# peltier.net
KiCad netlist of a schematic drawn in EAGLE
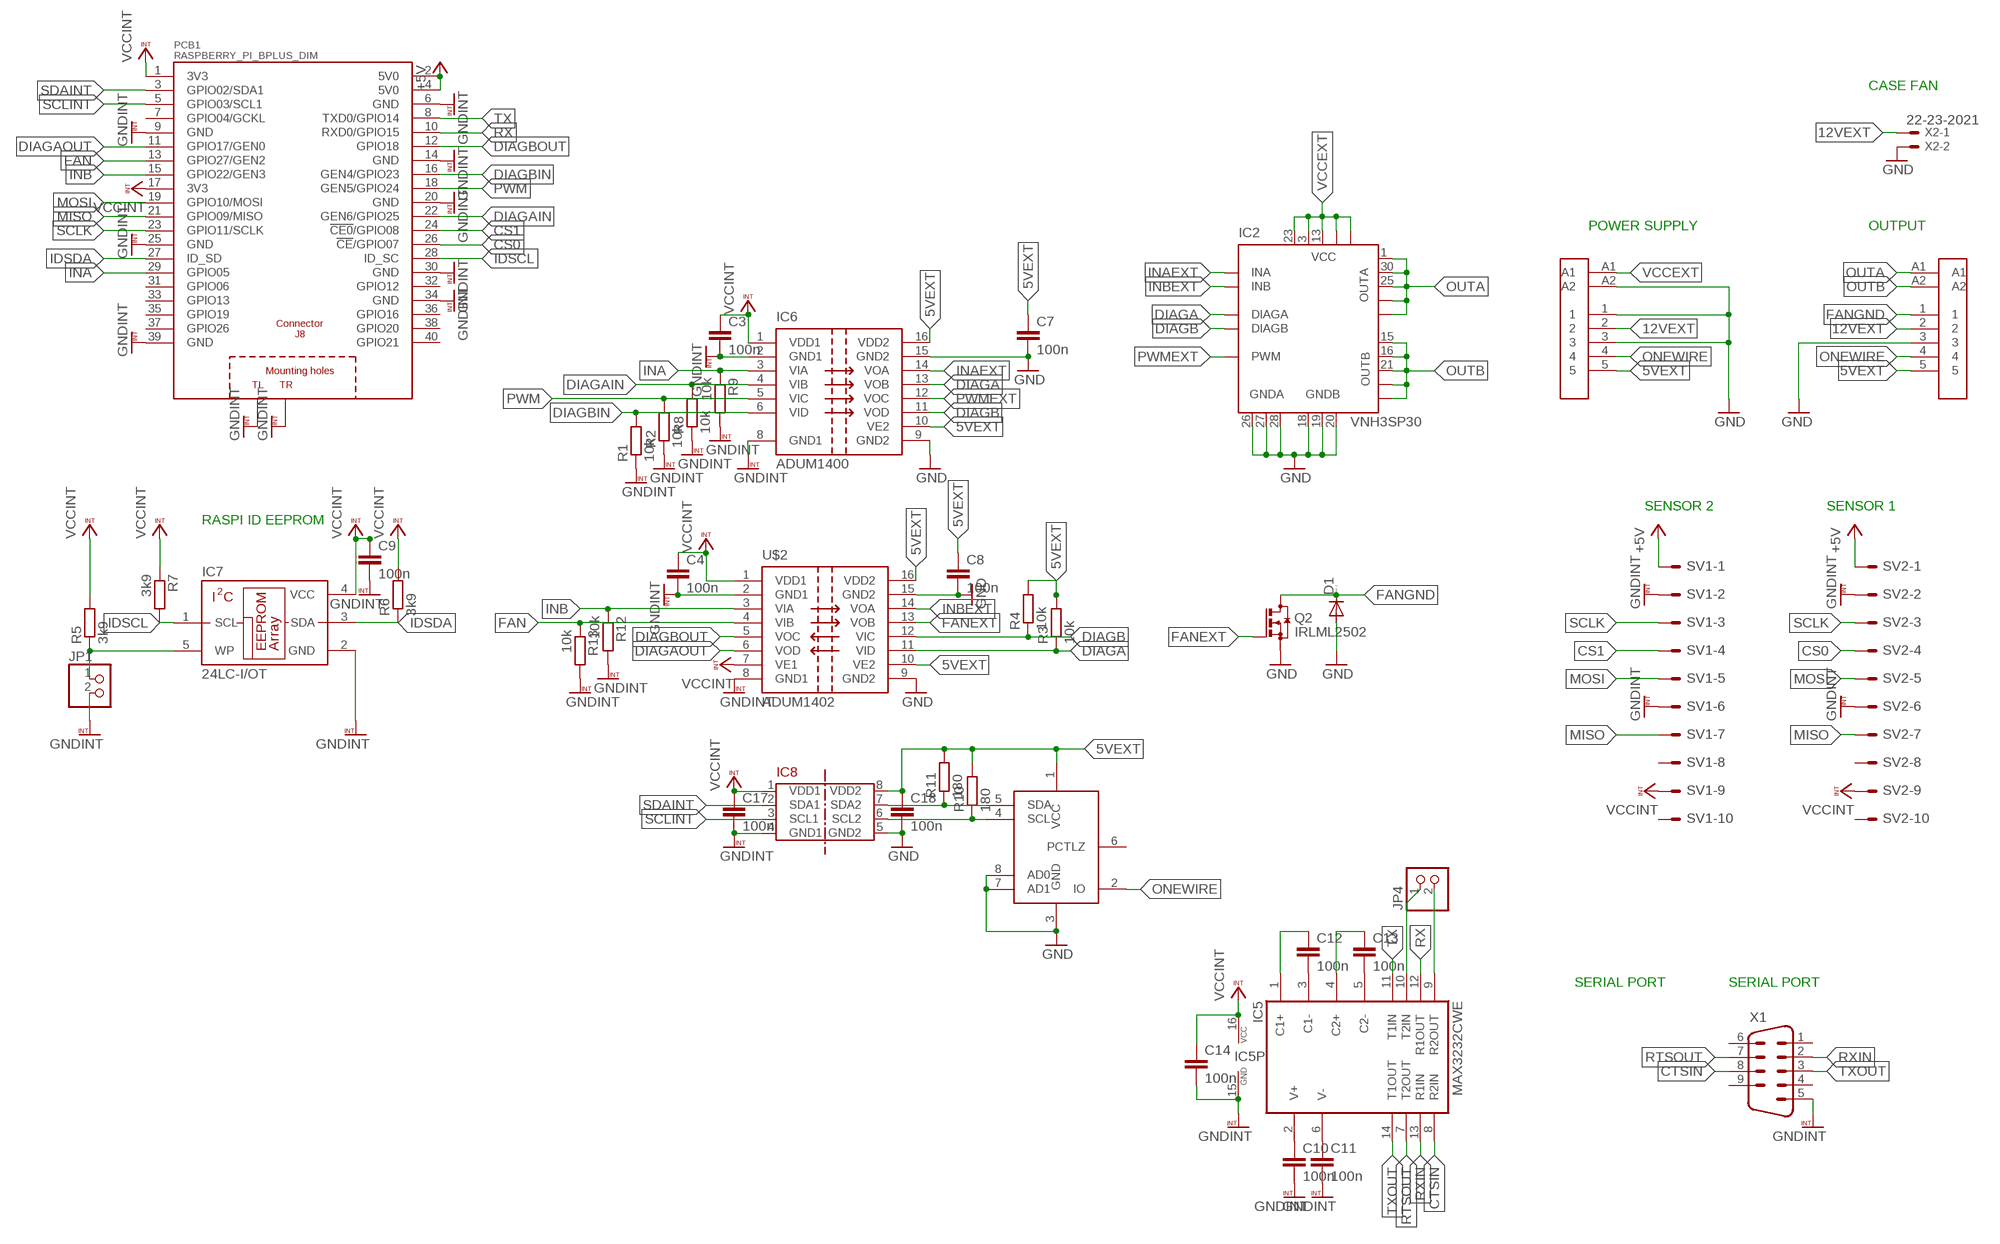
[diagram p0: schematic, sheet 1]

(export (version "E")
  (design (tool "Eeschema 10.0.6"))
  (components
    (comp (ref "C3")
      (value "100n")
      (footprint "eagle-import:C0805")
      (libsource (lib "eagle-import") (part "C-EUC0805"))
    )
    (comp (ref "C4")
      (value "100n")
      (footprint "eagle-import:C0805")
      (libsource (lib "eagle-import") (part "C-EUC0805"))
    )
    (comp (ref "C7")
      (value "100n")
      (footprint "eagle-import:C0805")
      (libsource (lib "eagle-import") (part "C-EUC0805"))
    )
    (comp (ref "C8")
      (value "100n")
      (footprint "eagle-import:C0805")
      (libsource (lib "eagle-import") (part "C-EUC0805"))
    )
    (comp (ref "C9")
      (value "100n")
      (footprint "eagle-import:C0805")
      (libsource (lib "eagle-import") (part "C-EUC0805"))
    )
    (comp (ref "C10")
      (value "100n")
      (footprint "eagle-import:C0805")
      (libsource (lib "eagle-import") (part "C-EUC0805"))
    )
    (comp (ref "C11")
      (value "100n")
      (footprint "eagle-import:C0805")
      (libsource (lib "eagle-import") (part "C-EUC0805"))
    )
    (comp (ref "C12")
      (value "100n")
      (footprint "eagle-import:C0805")
      (libsource (lib "eagle-import") (part "C-EUC0805"))
    )
    (comp (ref "C13")
      (value "100n")
      (footprint "eagle-import:C0805")
      (libsource (lib "eagle-import") (part "C-EUC0805"))
    )
    (comp (ref "C14")
      (value "100n")
      (footprint "eagle-import:C0805")
      (libsource (lib "eagle-import") (part "C-EUC0805"))
    )
    (comp (ref "C17")
      (value "100n")
      (footprint "eagle-import:C0805")
      (libsource (lib "eagle-import") (part "C-EUC0805"))
    )
    (comp (ref "C18")
      (value "100n")
      (footprint "eagle-import:C0805")
      (libsource (lib "eagle-import") (part "C-EUC0805"))
    )
    (comp (ref "D1")
      (value "DIODE-MINIMELF")
      (footprint "eagle-import:MINIMELF")
      (libsource (lib "eagle-import") (part "DIODE-MINIMELF"))
    )
    (comp (ref "IC2")
      (value "VNH3SP30")
      (footprint "eagle-import:MULTIPOWERSO-30")
      (fields (field (name "MPN") "VNH3SP30-E"))
      (libsource (lib "eagle-import") (part "VNH3SP30"))
    )
    (comp (ref "IC5")
      (value "MAX3232CWE")
      (footprint "eagle-import:SO16L")
      (fields (field (name "MF") "MAXIM") (field (name "MPN") "MAX3232CWE+"))
      (libsource (lib "eagle-import") (part "MAX3232WEC"))
    )
    (comp (ref "IC6")
      (value "ADUM1400")
      (footprint "eagle-import:SO16W")
      (libsource (lib "eagle-import") (part "ADUM1400"))
    )
    (comp (ref "IC7")
      (value "24LC-I/OT")
      (footprint "eagle-import:SOT23-5")
      (libsource (lib "eagle-import") (part "24LC-I/OT"))
    )
    (comp (ref "IC8")
      (value "ADUM1250")
      (footprint "eagle-import:SO08")
      (libsource (lib "eagle-import") (part "ADUM1250"))
    )
    (comp (ref "JP1")
      (value "PINHD-1X2")
      (footprint "eagle-import:1X02")
      (libsource (lib "eagle-import") (part "PINHD-1X2"))
    )
    (comp (ref "JP4")
      (value "PINHD-1X2")
      (footprint "eagle-import:1X02")
      (libsource (lib "eagle-import") (part "PINHD-1X2"))
    )
    (comp (ref "PCB1")
      (value "RASPBERRY_PI_BPLUS_DIM")
      (footprint "eagle-import:RASPBERRY_PI_BPLUS_DIM")
      (libsource (lib "eagle-import") (part "RASPBERRY_PI_BPLUS_DIM"))
    )
    (comp (ref "Q2")
      (value "IRLML2502")
      (footprint "eagle-import:SOT23")
      (libsource (lib "eagle-import") (part "BSS123"))
    )
    (comp (ref "R1")
      (value "10k")
      (footprint "eagle-import:R0603")
      (libsource (lib "eagle-import") (part "R-EU_R0603"))
    )
    (comp (ref "R2")
      (value "10k")
      (footprint "eagle-import:R0603")
      (libsource (lib "eagle-import") (part "R-EU_R0603"))
    )
    (comp (ref "R3")
      (value "10k")
      (footprint "eagle-import:R0805")
      (libsource (lib "eagle-import") (part "R-EU_R0805"))
    )
    (comp (ref "R4")
      (value "10k")
      (footprint "eagle-import:R0805")
      (libsource (lib "eagle-import") (part "R-EU_R0805"))
    )
    (comp (ref "R5")
      (value "3k9")
      (footprint "eagle-import:R0805")
      (libsource (lib "eagle-import") (part "R-EU_R0805"))
    )
    (comp (ref "R6")
      (value "3k9")
      (footprint "eagle-import:R0805")
      (libsource (lib "eagle-import") (part "R-EU_R0805"))
    )
    (comp (ref "R7")
      (value "3k9")
      (footprint "eagle-import:R0805")
      (libsource (lib "eagle-import") (part "R-EU_R0805"))
    )
    (comp (ref "R8")
      (value "10k")
      (footprint "eagle-import:R0603")
      (libsource (lib "eagle-import") (part "R-EU_R0603"))
    )
    (comp (ref "R9")
      (value "10k")
      (footprint "eagle-import:R0603")
      (libsource (lib "eagle-import") (part "R-EU_R0603"))
    )
    (comp (ref "R10")
      (value "180")
      (footprint "eagle-import:R0805")
      (libsource (lib "eagle-import") (part "R-EU_R0805"))
    )
    (comp (ref "R11")
      (value "180")
      (footprint "eagle-import:R0805")
      (libsource (lib "eagle-import") (part "R-EU_R0805"))
    )
    (comp (ref "R12")
      (value "10k")
      (footprint "eagle-import:R0603")
      (libsource (lib "eagle-import") (part "R-EU_R0603"))
    )
    (comp (ref "R13")
      (value "10k")
      (footprint "eagle-import:R0603")
      (libsource (lib "eagle-import") (part "R-EU_R0603"))
    )
    (comp (ref "SV1")
      (value "ML10E")
      (footprint "eagle-import:ML10")
      (libsource (lib "eagle-import") (part "ML10E"))
    )
    (comp (ref "SV2")
      (value "ML10E")
      (footprint "eagle-import:ML10")
      (libsource (lib "eagle-import") (part "ML10E"))
    )
    (comp (ref "U$2")
      (value "ADUM1402")
      (footprint "eagle-import:SO16W")
      (libsource (lib "eagle-import") (part "ADUM1402"))
    )
    (comp (ref "U$4")
      (value "7W2-F")
      (footprint "eagle-import:7W2-F")
      (libsource (lib "eagle-import") (part "7W2-F"))
    )
    (comp (ref "U$6")
      (value "7W2-M")
      (footprint "eagle-import:7W2-M")
      (libsource (lib "eagle-import") (part "7W2-M"))
    )
    (comp (ref "U$15")
      (value "DS2483-100")
      (footprint "eagle-import:SO-08")
      (libsource (lib "eagle-import") (part "DS2483-100"))
    )
    (comp (ref "X1")
      (value "M09HP")
      (footprint "eagle-import:M09HP")
      (libsource (lib "eagle-import") (part "M09HP"))
    )
    (comp (ref "X2")
      (value "22-23-2021")
      (footprint "eagle-import:22-23-2021")
      (fields (field (name "MF") "MOLEX"))
      (libsource (lib "eagle-import") (part "22-23-2021"))
    )
  )
  (nets
    (net (code "1") (name "+5V") (class "Default")
      (node (ref "PCB1") (pin "2") (pinfunction "5V0_2") (pintype "power_in"))
      (node (ref "PCB1") (pin "4") (pinfunction "5V0_4") (pintype "power_in"))
      (node (ref "SV1") (pin "1") (pinfunction "S_1") (pintype "passive"))
      (node (ref "SV2") (pin "1") (pinfunction "S_1") (pintype "passive"))
    )
    (net (code "2") (name "5VEXT") (class "Default")
      (node (ref "C18") (pin "1") (pinfunction "1_1") (pintype "passive"))
      (node (ref "C7") (pin "1") (pinfunction "1_1") (pintype "passive"))
      (node (ref "C8") (pin "1") (pinfunction "1_1") (pintype "passive"))
      (node (ref "IC6") (pin "10") (pinfunction "VE2_10") (pintype "passive"))
      (node (ref "IC6") (pin "16") (pinfunction "VDD2_16") (pintype "power_in"))
      (node (ref "IC8") (pin "8") (pinfunction "VDD2_8") (pintype "power_in"))
      (node (ref "R10") (pin "2") (pinfunction "2_2") (pintype "passive"))
      (node (ref "R11") (pin "2") (pinfunction "2_2") (pintype "passive"))
      (node (ref "R3") (pin "2") (pinfunction "2_2") (pintype "passive"))
      (node (ref "R4") (pin "2") (pinfunction "2_2") (pintype "passive"))
      (node (ref "U$15") (pin "1") (pinfunction "VCC_1") (pintype "bidirectional"))
      (node (ref "U$2") (pin "10") (pinfunction "VE2_10") (pintype "passive"))
      (node (ref "U$2") (pin "16") (pinfunction "VDD2_16") (pintype "power_in"))
      (node (ref "U$4") (pin "5") (pinfunction "5_5") (pintype "bidirectional"))
      (node (ref "U$6") (pin "5") (pinfunction "5_5") (pintype "bidirectional"))
    )
    (net (code "3") (name "12VEXT") (class "Default")
      (node (ref "U$4") (pin "2") (pinfunction "2_2") (pintype "bidirectional"))
      (node (ref "U$6") (pin "2") (pinfunction "2_2") (pintype "bidirectional"))
      (node (ref "X2") (pin "1") (pinfunction "S_1") (pintype "passive"))
    )
    (net (code "4") (name "CS0") (class "Default")
      (node (ref "PCB1") (pin "26") (pinfunction "~{CE}/GPIO07_26") (pintype "bidirectional"))
      (node (ref "SV2") (pin "4") (pinfunction "S_4") (pintype "passive"))
    )
    (net (code "5") (name "CS1") (class "Default")
      (node (ref "PCB1") (pin "24") (pinfunction "~{CE0}/GPIO08_24") (pintype "bidirectional"))
      (node (ref "SV1") (pin "4") (pinfunction "S_4") (pintype "passive"))
    )
    (net (code "6") (name "CTSIN") (class "Default")
      (node (ref "IC5") (pin "8") (pinfunction "R2IN_8") (pintype "input"))
      (node (ref "X1") (pin "8") (pinfunction "8_8") (pintype "passive"))
    )
    (net (code "7") (name "DIAGA") (class "Default")
      (node (ref "IC2") (pin "6") (pinfunction "DIAGA_6") (pintype "open_collector"))
      (node (ref "IC6") (pin "13") (pinfunction "VOB_13") (pintype "output"))
      (node (ref "R3") (pin "1") (pinfunction "1_1") (pintype "passive"))
      (node (ref "U$2") (pin "11") (pinfunction "VID_11") (pintype "input"))
    )
    (net (code "8") (name "DIAGAIN") (class "Default")
      (node (ref "IC6") (pin "4") (pinfunction "VIB_4") (pintype "input"))
      (node (ref "PCB1") (pin "22") (pinfunction "GEN6/GPIO25_22") (pintype "bidirectional"))
      (node (ref "R8") (pin "2") (pinfunction "2_2") (pintype "passive"))
    )
    (net (code "9") (name "DIAGAOUT") (class "Default")
      (node (ref "PCB1") (pin "11") (pinfunction "GPIO17/GEN0_11") (pintype "bidirectional"))
      (node (ref "U$2") (pin "6") (pinfunction "VOD_6") (pintype "output"))
    )
    (net (code "10") (name "DIAGB") (class "Default")
      (node (ref "IC2") (pin "10") (pinfunction "DIAGB_10") (pintype "open_collector"))
      (node (ref "IC6") (pin "11") (pinfunction "VOD_11") (pintype "output"))
      (node (ref "R4") (pin "1") (pinfunction "1_1") (pintype "passive"))
      (node (ref "U$2") (pin "12") (pinfunction "VIC_12") (pintype "input"))
    )
    (net (code "11") (name "DIAGBIN") (class "Default")
      (node (ref "IC6") (pin "6") (pinfunction "VID_6") (pintype "input"))
      (node (ref "PCB1") (pin "16") (pinfunction "GEN4/GPIO23_16") (pintype "bidirectional"))
      (node (ref "R1") (pin "2") (pinfunction "2_2") (pintype "passive"))
    )
    (net (code "12") (name "DIAGBOUT") (class "Default")
      (node (ref "PCB1") (pin "12") (pinfunction "GPIO18_12") (pintype "bidirectional"))
      (node (ref "U$2") (pin "5") (pinfunction "VOC_5") (pintype "output"))
    )
    (net (code "13") (name "FAN") (class "Default")
      (node (ref "PCB1") (pin "13") (pinfunction "GPIO27/GEN2_13") (pintype "bidirectional"))
      (node (ref "R13") (pin "1") (pinfunction "1_1") (pintype "passive"))
      (node (ref "U$2") (pin "4") (pinfunction "VIB_4") (pintype "input"))
    )
    (net (code "14") (name "FANEXT") (class "Default")
      (node (ref "Q2") (pin "1") (pinfunction "G_1") (pintype "passive"))
      (node (ref "U$2") (pin "13") (pinfunction "VOB_13") (pintype "output"))
    )
    (net (code "15") (name "FANGND") (class "Default")
      (node (ref "D1") (pin "C") (pinfunction "C_C") (pintype "passive"))
      (node (ref "Q2") (pin "3") (pinfunction "D_3") (pintype "passive"))
      (node (ref "U$4") (pin "1") (pinfunction "1_1") (pintype "bidirectional"))
    )
    (net (code "16") (name "GND") (class "Default")
      (node (ref "C18") (pin "2") (pinfunction "2_2") (pintype "passive"))
      (node (ref "C7") (pin "2") (pinfunction "2_2") (pintype "passive"))
      (node (ref "C8") (pin "2") (pinfunction "2_2") (pintype "passive"))
      (node (ref "D1") (pin "A") (pinfunction "A_A") (pintype "passive"))
      (node (ref "IC2") (pin "18") (pinfunction "GNDB_18") (pintype "power_in"))
      (node (ref "IC2") (pin "19") (pinfunction "GNDB_19") (pintype "power_in"))
      (node (ref "IC2") (pin "20") (pinfunction "GNDB_20") (pintype "power_in"))
      (node (ref "IC2") (pin "26") (pinfunction "GNDA_26") (pintype "power_in"))
      (node (ref "IC2") (pin "27") (pinfunction "GNDA_27") (pintype "power_in"))
      (node (ref "IC2") (pin "28") (pinfunction "GNDA_28") (pintype "power_in"))
      (node (ref "IC6") (pin "15") (pinfunction "GND2_15") (pintype "power_in"))
      (node (ref "IC6") (pin "9") (pinfunction "GND2_9") (pintype "power_in"))
      (node (ref "IC8") (pin "5") (pinfunction "GND2_5") (pintype "power_in"))
      (node (ref "Q2") (pin "2") (pinfunction "S_2") (pintype "passive"))
      (node (ref "U$15") (pin "3") (pinfunction "GND_3") (pintype "bidirectional"))
      (node (ref "U$15") (pin "7") (pinfunction "AD1_7") (pintype "bidirectional"))
      (node (ref "U$15") (pin "8") (pinfunction "AD0_8") (pintype "bidirectional"))
      (node (ref "U$2") (pin "15") (pinfunction "GND2_15") (pintype "power_in"))
      (node (ref "U$2") (pin "9") (pinfunction "GND2_9") (pintype "power_in"))
      (node (ref "U$4") (pin "3") (pinfunction "3_3") (pintype "bidirectional"))
      (node (ref "U$6") (pin "1") (pinfunction "1_1") (pintype "bidirectional"))
      (node (ref "U$6") (pin "3") (pinfunction "3_3") (pintype "bidirectional"))
      (node (ref "U$6") (pin "A2") (pinfunction "A2_A2") (pintype "bidirectional"))
      (node (ref "X2") (pin "2") (pinfunction "S_2") (pintype "passive"))
    )
    (net (code "17") (name "GNDINT") (class "Default")
      (node (ref "C10") (pin "2") (pinfunction "2_2") (pintype "passive"))
      (node (ref "C11") (pin "2") (pinfunction "2_2") (pintype "passive"))
      (node (ref "C14") (pin "2") (pinfunction "2_2") (pintype "passive"))
      (node (ref "C17") (pin "2") (pinfunction "2_2") (pintype "passive"))
      (node (ref "C3") (pin "2") (pinfunction "2_2") (pintype "passive"))
      (node (ref "C4") (pin "2") (pinfunction "2_2") (pintype "passive"))
      (node (ref "C9") (pin "2") (pinfunction "2_2") (pintype "passive"))
      (node (ref "IC5") (pin "15") (pinfunction "GND_15") (pintype "power_in"))
      (node (ref "IC6") (pin "2") (pinfunction "GND1_2") (pintype "power_in"))
      (node (ref "IC6") (pin "8") (pinfunction "GND1_8") (pintype "power_in"))
      (node (ref "IC7") (pin "2") (pinfunction "GND_2") (pintype "power_in"))
      (node (ref "IC8") (pin "4") (pinfunction "GND1_4") (pintype "power_in"))
      (node (ref "JP1") (pin "2") (pinfunction "2_2") (pintype "passive"))
      (node (ref "PCB1") (pin "14") (pinfunction "GND_14") (pintype "power_in"))
      (node (ref "PCB1") (pin "20") (pinfunction "GND_20") (pintype "power_in"))
      (node (ref "PCB1") (pin "25") (pinfunction "GND_25") (pintype "power_in"))
      (node (ref "PCB1") (pin "30") (pinfunction "GND_30") (pintype "power_in"))
      (node (ref "PCB1") (pin "34") (pinfunction "GND_34") (pintype "power_in"))
      (node (ref "PCB1") (pin "39") (pinfunction "GND_39") (pintype "power_in"))
      (node (ref "PCB1") (pin "6") (pinfunction "GND_6") (pintype "power_in"))
      (node (ref "PCB1") (pin "9") (pinfunction "GND_9") (pintype "power_in"))
      (node (ref "PCB1") (pin "PE_TL") (pinfunction "TL_PE_TL") (pintype "bidirectional"))
      (node (ref "PCB1") (pin "PE_TR") (pinfunction "TR_PE_TR") (pintype "bidirectional"))
      (node (ref "R1") (pin "1") (pinfunction "1_1") (pintype "passive"))
      (node (ref "R12") (pin "2") (pinfunction "2_2") (pintype "passive"))
      (node (ref "R13") (pin "2") (pinfunction "2_2") (pintype "passive"))
      (node (ref "R2") (pin "1") (pinfunction "1_1") (pintype "passive"))
      (node (ref "R8") (pin "1") (pinfunction "1_1") (pintype "passive"))
      (node (ref "R9") (pin "2") (pinfunction "2_2") (pintype "passive"))
      (node (ref "SV1") (pin "2") (pinfunction "S_2") (pintype "passive"))
      (node (ref "SV1") (pin "6") (pinfunction "S_6") (pintype "passive"))
      (node (ref "SV2") (pin "2") (pinfunction "S_2") (pintype "passive"))
      (node (ref "SV2") (pin "6") (pinfunction "S_6") (pintype "passive"))
      (node (ref "U$2") (pin "2") (pinfunction "GND1_2") (pintype "power_in"))
      (node (ref "U$2") (pin "8") (pinfunction "GND1_8") (pintype "power_in"))
      (node (ref "X1") (pin "5") (pinfunction "5_5") (pintype "passive"))
    )
    (net (code "18") (name "IDSCL") (class "Default")
      (node (ref "IC7") (pin "1") (pinfunction "SCL_1") (pintype "bidirectional"))
      (node (ref "PCB1") (pin "28") (pinfunction "ID_SC_28") (pintype "bidirectional"))
      (node (ref "R7") (pin "2") (pinfunction "2_2") (pintype "passive"))
    )
    (net (code "19") (name "IDSDA") (class "Default")
      (node (ref "IC7") (pin "3") (pinfunction "SDA_3") (pintype "bidirectional"))
      (node (ref "PCB1") (pin "27") (pinfunction "ID_SD_27") (pintype "bidirectional"))
      (node (ref "R6") (pin "1") (pinfunction "1_1") (pintype "passive"))
    )
    (net (code "20") (name "INA") (class "Default")
      (node (ref "IC6") (pin "3") (pinfunction "VIA_3") (pintype "input"))
      (node (ref "PCB1") (pin "29") (pinfunction "GPIO05_29") (pintype "bidirectional"))
      (node (ref "R9") (pin "1") (pinfunction "1_1") (pintype "passive"))
    )
    (net (code "21") (name "INAEXT") (class "Default")
      (node (ref "IC2") (pin "5") (pinfunction "INA_5") (pintype "input"))
      (node (ref "IC6") (pin "14") (pinfunction "VOA_14") (pintype "output"))
    )
    (net (code "22") (name "INB") (class "Default")
      (node (ref "PCB1") (pin "15") (pinfunction "GPIO22/GEN3_15") (pintype "bidirectional"))
      (node (ref "R12") (pin "1") (pinfunction "1_1") (pintype "passive"))
      (node (ref "U$2") (pin "3") (pinfunction "VIA_3") (pintype "input"))
    )
    (net (code "23") (name "INBEXT") (class "Default")
      (node (ref "IC2") (pin "11") (pinfunction "INB_11") (pintype "input"))
      (node (ref "U$2") (pin "14") (pinfunction "VOA_14") (pintype "output"))
    )
    (net (code "24") (name "MISO") (class "Default")
      (node (ref "PCB1") (pin "21") (pinfunction "GPIO09/MISO_21") (pintype "bidirectional"))
      (node (ref "SV1") (pin "7") (pinfunction "S_7") (pintype "passive"))
      (node (ref "SV2") (pin "7") (pinfunction "S_7") (pintype "passive"))
    )
    (net (code "25") (name "MOSI") (class "Default")
      (node (ref "PCB1") (pin "19") (pinfunction "GPIO10/MOSI_19") (pintype "bidirectional"))
      (node (ref "SV1") (pin "5") (pinfunction "S_5") (pintype "passive"))
      (node (ref "SV2") (pin "5") (pinfunction "S_5") (pintype "passive"))
    )
    (net (code "26") (name "Net-(IC5A-C1+)") (class "Default")
      (node (ref "C12") (pin "1") (pinfunction "1_1") (pintype "passive"))
      (node (ref "IC5") (pin "1") (pinfunction "C1+_1") (pintype "bidirectional"))
    )
    (net (code "27") (name "Net-(IC5A-C1-)") (class "Default")
      (node (ref "C12") (pin "2") (pinfunction "2_2") (pintype "passive"))
      (node (ref "IC5") (pin "3") (pinfunction "C1-_3") (pintype "bidirectional"))
    )
    (net (code "28") (name "Net-(IC5A-C2+)") (class "Default")
      (node (ref "C13") (pin "1") (pinfunction "1_1") (pintype "passive"))
      (node (ref "IC5") (pin "4") (pinfunction "C2+_4") (pintype "bidirectional"))
    )
    (net (code "29") (name "Net-(IC5A-C2-)") (class "Default")
      (node (ref "C13") (pin "2") (pinfunction "2_2") (pintype "passive"))
      (node (ref "IC5") (pin "5") (pinfunction "C2-_5") (pintype "bidirectional"))
    )
    (net (code "30") (name "Net-(IC5A-R2OUT)") (class "Default")
      (node (ref "IC5") (pin "9") (pinfunction "R2OUT_9") (pintype "output"))
      (node (ref "JP4") (pin "2") (pinfunction "2_2") (pintype "passive"))
    )
    (net (code "31") (name "Net-(IC5A-T2IN)") (class "Default")
      (node (ref "IC5") (pin "10") (pinfunction "T2IN_10") (pintype "input"))
      (node (ref "JP4") (pin "1") (pinfunction "1_1") (pintype "passive"))
    )
    (net (code "32") (name "Net-(IC5A-V+)") (class "Default")
      (node (ref "C10") (pin "1") (pinfunction "1_1") (pintype "passive"))
      (node (ref "IC5") (pin "2") (pinfunction "V+_2") (pintype "bidirectional"))
    )
    (net (code "33") (name "Net-(IC5A-V-)") (class "Default")
      (node (ref "C11") (pin "1") (pinfunction "1_1") (pintype "passive"))
      (node (ref "IC5") (pin "6") (pinfunction "V-_6") (pintype "bidirectional"))
    )
    (net (code "34") (name "Net-(IC7-WP)") (class "Default")
      (node (ref "IC7") (pin "5") (pinfunction "WP_5") (pintype "bidirectional"))
      (node (ref "JP1") (pin "1") (pinfunction "1_1") (pintype "passive"))
      (node (ref "R5") (pin "1") (pinfunction "1_1") (pintype "passive"))
    )
    (net (code "35") (name "Net-(IC8-SCL2)") (class "Default")
      (node (ref "IC8") (pin "6") (pinfunction "SCL2_6") (pintype "bidirectional"))
      (node (ref "R10") (pin "1") (pinfunction "1_1") (pintype "passive"))
      (node (ref "U$15") (pin "4") (pinfunction "SCL_4") (pintype "bidirectional"))
    )
    (net (code "36") (name "Net-(IC8-SDA2)") (class "Default")
      (node (ref "IC8") (pin "7") (pinfunction "SDA2_7") (pintype "bidirectional"))
      (node (ref "R11") (pin "1") (pinfunction "1_1") (pintype "passive"))
      (node (ref "U$15") (pin "5") (pinfunction "SDA_5") (pintype "bidirectional"))
    )
    (net (code "37") (name "ONEWIRE") (class "Default")
      (node (ref "U$15") (pin "2") (pinfunction "IO_2") (pintype "bidirectional"))
      (node (ref "U$4") (pin "4") (pinfunction "4_4") (pintype "bidirectional"))
      (node (ref "U$6") (pin "4") (pinfunction "4_4") (pintype "bidirectional"))
    )
    (net (code "38") (name "OUTA") (class "Default")
      (node (ref "IC2") (pin "1") (pinfunction "OUTA_1") (pintype "output"))
      (node (ref "IC2") (pin "25") (pinfunction "OUTA_25") (pintype "passive"))
      (node (ref "IC2") (pin "30") (pinfunction "OUTA_30") (pintype "passive"))
      (node (ref "IC2") (pin "OUTA") (pinfunction "OUTA_OUTA") (pintype "passive"))
      (node (ref "IC2") (pin "OUTA@1") (pinfunction "OUTA_OUTA@1") (pintype "passive"))
      (node (ref "U$4") (pin "A1") (pinfunction "A1_A1") (pintype "bidirectional"))
    )
    (net (code "39") (name "OUTB") (class "Default")
      (node (ref "IC2") (pin "15") (pinfunction "OUTB_15") (pintype "output"))
      (node (ref "IC2") (pin "16") (pinfunction "OUTB_16") (pintype "passive"))
      (node (ref "IC2") (pin "21") (pinfunction "OUTB_21") (pintype "passive"))
      (node (ref "IC2") (pin "OUTB") (pinfunction "OUTB_OUTB") (pintype "passive"))
      (node (ref "IC2") (pin "OUTB@1") (pinfunction "OUTB_OUTB@1") (pintype "passive"))
      (node (ref "U$4") (pin "A2") (pinfunction "A2_A2") (pintype "bidirectional"))
    )
    (net (code "40") (name "PWM") (class "Default")
      (node (ref "IC6") (pin "5") (pinfunction "VIC_5") (pintype "input"))
      (node (ref "PCB1") (pin "18") (pinfunction "GEN5/GPIO24_18") (pintype "bidirectional"))
      (node (ref "R2") (pin "2") (pinfunction "2_2") (pintype "passive"))
    )
    (net (code "41") (name "PWMEXT") (class "Default")
      (node (ref "IC2") (pin "8") (pinfunction "PWM_8") (pintype "input"))
      (node (ref "IC6") (pin "12") (pinfunction "VOC_12") (pintype "output"))
    )
    (net (code "42") (name "RTSOUT") (class "Default")
      (node (ref "IC5") (pin "7") (pinfunction "T2OUT_7") (pintype "output"))
      (node (ref "X1") (pin "7") (pinfunction "7_7") (pintype "passive"))
    )
    (net (code "43") (name "RX") (class "Default")
      (node (ref "IC5") (pin "12") (pinfunction "R1OUT_12") (pintype "output"))
      (node (ref "PCB1") (pin "10") (pinfunction "RXD0/GPIO15_10") (pintype "bidirectional"))
    )
    (net (code "44") (name "RXIN") (class "Default")
      (node (ref "IC5") (pin "13") (pinfunction "R1IN_13") (pintype "input"))
      (node (ref "X1") (pin "2") (pinfunction "2_2") (pintype "passive"))
    )
    (net (code "45") (name "SCLINT") (class "Default")
      (node (ref "IC8") (pin "3") (pinfunction "SCL1_3") (pintype "bidirectional"))
      (node (ref "PCB1") (pin "5") (pinfunction "GPIO03/SCL1_5") (pintype "bidirectional"))
    )
    (net (code "46") (name "SCLK") (class "Default")
      (node (ref "PCB1") (pin "23") (pinfunction "GPIO11/SCLK_23") (pintype "bidirectional"))
      (node (ref "SV1") (pin "3") (pinfunction "S_3") (pintype "passive"))
      (node (ref "SV2") (pin "3") (pinfunction "S_3") (pintype "passive"))
    )
    (net (code "47") (name "SDAINT") (class "Default")
      (node (ref "IC8") (pin "2") (pinfunction "SDA1_2") (pintype "bidirectional"))
      (node (ref "PCB1") (pin "3") (pinfunction "GPIO02/SDA1_3") (pintype "bidirectional"))
    )
    (net (code "48") (name "TX") (class "Default")
      (node (ref "IC5") (pin "11") (pinfunction "T1IN_11") (pintype "input"))
      (node (ref "PCB1") (pin "8") (pinfunction "TXD0/GPIO14_8") (pintype "bidirectional"))
    )
    (net (code "49") (name "TXOUT") (class "Default")
      (node (ref "IC5") (pin "14") (pinfunction "T1OUT_14") (pintype "output"))
      (node (ref "X1") (pin "3") (pinfunction "3_3") (pintype "passive"))
    )
    (net (code "50") (name "VCCEXT") (class "Default")
      (node (ref "IC2") (pin "13") (pinfunction "VCC_13") (pintype "power_in"))
      (node (ref "IC2") (pin "23") (pinfunction "VCC_23") (pintype "power_in"))
      (node (ref "IC2") (pin "3") (pinfunction "VCC_3") (pintype "power_in"))
      (node (ref "IC2") (pin "VCC") (pinfunction "VCC_VCC") (pintype "power_in"))
      (node (ref "IC2") (pin "VCC@1") (pinfunction "VCC_VCC@1") (pintype "power_in"))
      (node (ref "U$6") (pin "A1") (pinfunction "A1_A1") (pintype "bidirectional"))
    )
    (net (code "51") (name "VCCINT") (class "Default")
      (node (ref "C14") (pin "1") (pinfunction "1_1") (pintype "passive"))
      (node (ref "C17") (pin "1") (pinfunction "1_1") (pintype "passive"))
      (node (ref "C3") (pin "1") (pinfunction "1_1") (pintype "passive"))
      (node (ref "C4") (pin "1") (pinfunction "1_1") (pintype "passive"))
      (node (ref "C9") (pin "1") (pinfunction "1_1") (pintype "passive"))
      (node (ref "IC5") (pin "16") (pinfunction "VCC_16") (pintype "power_in"))
      (node (ref "IC6") (pin "1") (pinfunction "VDD1_1") (pintype "power_in"))
      (node (ref "IC7") (pin "4") (pinfunction "VCC_4") (pintype "power_in"))
      (node (ref "IC8") (pin "1") (pinfunction "VDD1_1") (pintype "power_in"))
      (node (ref "PCB1") (pin "1") (pinfunction "3V3_1") (pintype "power_in"))
      (node (ref "PCB1") (pin "17") (pinfunction "3V3_17") (pintype "power_in"))
      (node (ref "R5") (pin "2") (pinfunction "2_2") (pintype "passive"))
      (node (ref "R6") (pin "2") (pinfunction "2_2") (pintype "passive"))
      (node (ref "R7") (pin "1") (pinfunction "1_1") (pintype "passive"))
      (node (ref "SV1") (pin "9") (pinfunction "S_9") (pintype "passive"))
      (node (ref "SV2") (pin "9") (pinfunction "S_9") (pintype "passive"))
      (node (ref "U$2") (pin "1") (pinfunction "VDD1_1") (pintype "power_in"))
      (node (ref "U$2") (pin "7") (pinfunction "VE1_7") (pintype "passive"))
    )
    (net (code "52") (name "unconnected-(PCB1-GPIO04{slash}GCKL-Pad7)") (class "Default")
      (node (ref "PCB1") (pin "7") (pinfunction "GPIO04/GCKL_7") (pintype "bidirectional"))
    )
    (net (code "53") (name "unconnected-(PCB1-GPIO06-Pad31)") (class "Default")
      (node (ref "PCB1") (pin "31") (pinfunction "GPIO06_31") (pintype "bidirectional"))
    )
    (net (code "54") (name "unconnected-(PCB1-GPIO12-Pad32)") (class "Default")
      (node (ref "PCB1") (pin "32") (pinfunction "GPIO12_32") (pintype "bidirectional"))
    )
    (net (code "55") (name "unconnected-(PCB1-GPIO13-Pad33)") (class "Default")
      (node (ref "PCB1") (pin "33") (pinfunction "GPIO13_33") (pintype "bidirectional"))
    )
    (net (code "56") (name "unconnected-(PCB1-GPIO16-Pad36)") (class "Default")
      (node (ref "PCB1") (pin "36") (pinfunction "GPIO16_36") (pintype "bidirectional"))
    )
    (net (code "57") (name "unconnected-(PCB1-GPIO19-Pad35)") (class "Default")
      (node (ref "PCB1") (pin "35") (pinfunction "GPIO19_35") (pintype "bidirectional"))
    )
    (net (code "58") (name "unconnected-(PCB1-GPIO20-Pad38)") (class "Default")
      (node (ref "PCB1") (pin "38") (pinfunction "GPIO20_38") (pintype "bidirectional"))
    )
    (net (code "59") (name "unconnected-(PCB1-GPIO21-Pad40)") (class "Default")
      (node (ref "PCB1") (pin "40") (pinfunction "GPIO21_40") (pintype "bidirectional"))
    )
    (net (code "60") (name "unconnected-(PCB1-GPIO26-Pad37)") (class "Default")
      (node (ref "PCB1") (pin "37") (pinfunction "GPIO26_37") (pintype "bidirectional"))
    )
    (net (code "61") (name "unconnected-(SV1B-S-Pad10)") (class "Default")
      (node (ref "SV1") (pin "10") (pinfunction "S_10") (pintype "passive"))
    )
    (net (code "62") (name "unconnected-(SV1I-S-Pad8)") (class "Default")
      (node (ref "SV1") (pin "8") (pinfunction "S_8") (pintype "passive"))
    )
    (net (code "63") (name "unconnected-(SV2B-S-Pad10)") (class "Default")
      (node (ref "SV2") (pin "10") (pinfunction "S_10") (pintype "passive"))
    )
    (net (code "64") (name "unconnected-(SV2I-S-Pad8)") (class "Default")
      (node (ref "SV2") (pin "8") (pinfunction "S_8") (pintype "passive"))
    )
    (net (code "65") (name "unconnected-(U$15-PCTLZ-Pad6)") (class "Default")
      (node (ref "U$15") (pin "6") (pinfunction "PCTLZ_6") (pintype "bidirectional"))
    )
    (net (code "66") (name "unconnected-(X1-Pad1)") (class "Default")
      (node (ref "X1") (pin "1") (pinfunction "1_1") (pintype "passive"))
    )
    (net (code "67") (name "unconnected-(X1-Pad4)") (class "Default")
      (node (ref "X1") (pin "4") (pinfunction "4_4") (pintype "passive"))
    )
    (net (code "68") (name "unconnected-(X1-Pad6)") (class "Default")
      (node (ref "X1") (pin "6") (pinfunction "6_6") (pintype "passive"))
    )
    (net (code "69") (name "unconnected-(X1-Pad9)") (class "Default")
      (node (ref "X1") (pin "9") (pinfunction "9_9") (pintype "passive"))
    )
  )
)
